# rj11.net
KiCad netlist of a schematic drawn in EAGLE
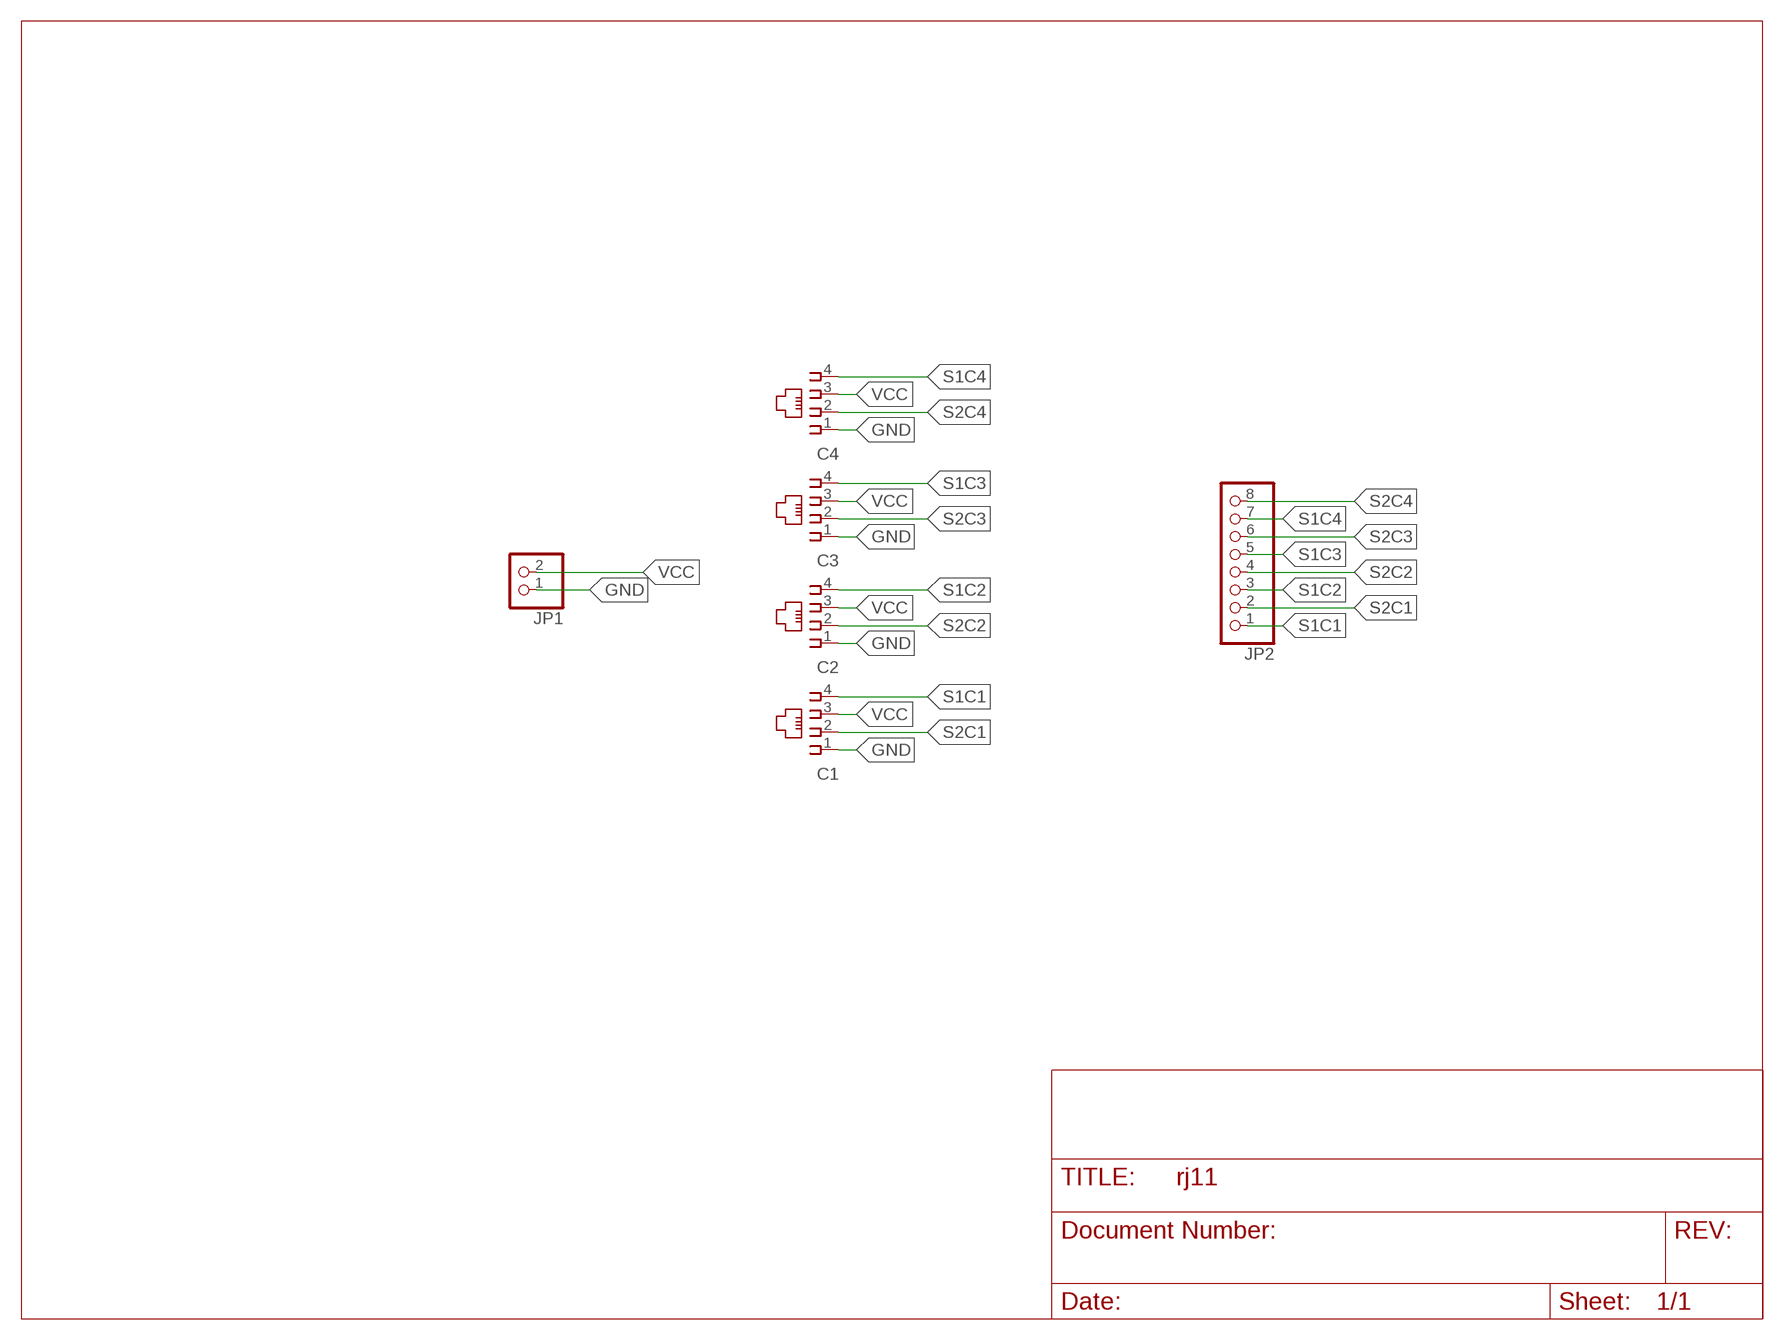
[diagram p0: schematic, sheet 1]

(export (version "E")
  (design (tool "Eeschema 10.0.6"))
  (components
    (comp (ref "C1")
      (value "14867")
      (footprint "eagle-import:14867")
      (libsource (lib "eagle-import") (part "14867"))
    )
    (comp (ref "C2")
      (value "14867")
      (footprint "eagle-import:14867")
      (libsource (lib "eagle-import") (part "14867"))
    )
    (comp (ref "C3")
      (value "14867")
      (footprint "eagle-import:14867")
      (libsource (lib "eagle-import") (part "14867"))
    )
    (comp (ref "C4")
      (value "14867")
      (footprint "eagle-import:14867")
      (libsource (lib "eagle-import") (part "14867"))
    )
    (comp (ref "JP1")
      (value "PINHD-1X2")
      (footprint "eagle-import:1X02")
      (libsource (lib "eagle-import") (part "PINHD-1X2"))
    )
    (comp (ref "JP2")
      (value "PINHD-1X8")
      (footprint "eagle-import:1X08")
      (libsource (lib "eagle-import") (part "PINHD-1X8"))
    )
  )
  (nets
    (net (code "1") (name "GND") (class "Default")
      (node (ref "C1") (pin "1") (pinfunction "1_1") (pintype "passive"))
      (node (ref "C2") (pin "1") (pinfunction "1_1") (pintype "passive"))
      (node (ref "C3") (pin "1") (pinfunction "1_1") (pintype "passive"))
      (node (ref "C4") (pin "1") (pinfunction "1_1") (pintype "passive"))
      (node (ref "JP1") (pin "1") (pinfunction "1_1") (pintype "passive"))
    )
    (net (code "2") (name "S1C1") (class "Default")
      (node (ref "C1") (pin "4") (pinfunction "4_4") (pintype "passive"))
      (node (ref "JP2") (pin "1") (pinfunction "1_1") (pintype "passive"))
    )
    (net (code "3") (name "S1C2") (class "Default")
      (node (ref "C2") (pin "4") (pinfunction "4_4") (pintype "passive"))
      (node (ref "JP2") (pin "3") (pinfunction "3_3") (pintype "passive"))
    )
    (net (code "4") (name "S1C3") (class "Default")
      (node (ref "C3") (pin "4") (pinfunction "4_4") (pintype "passive"))
      (node (ref "JP2") (pin "5") (pinfunction "5_5") (pintype "passive"))
    )
    (net (code "5") (name "S1C4") (class "Default")
      (node (ref "C4") (pin "4") (pinfunction "4_4") (pintype "passive"))
      (node (ref "JP2") (pin "7") (pinfunction "7_7") (pintype "passive"))
    )
    (net (code "6") (name "S2C1") (class "Default")
      (node (ref "C1") (pin "2") (pinfunction "2_2") (pintype "passive"))
      (node (ref "JP2") (pin "2") (pinfunction "2_2") (pintype "passive"))
    )
    (net (code "7") (name "S2C2") (class "Default")
      (node (ref "C2") (pin "2") (pinfunction "2_2") (pintype "passive"))
      (node (ref "JP2") (pin "4") (pinfunction "4_4") (pintype "passive"))
    )
    (net (code "8") (name "S2C3") (class "Default")
      (node (ref "C3") (pin "2") (pinfunction "2_2") (pintype "passive"))
      (node (ref "JP2") (pin "6") (pinfunction "6_6") (pintype "passive"))
    )
    (net (code "9") (name "S2C4") (class "Default")
      (node (ref "C4") (pin "2") (pinfunction "2_2") (pintype "passive"))
      (node (ref "JP2") (pin "8") (pinfunction "8_8") (pintype "passive"))
    )
    (net (code "10") (name "VCC") (class "Default")
      (node (ref "C1") (pin "3") (pinfunction "3_3") (pintype "passive"))
      (node (ref "C2") (pin "3") (pinfunction "3_3") (pintype "passive"))
      (node (ref "C3") (pin "3") (pinfunction "3_3") (pintype "passive"))
      (node (ref "C4") (pin "3") (pinfunction "3_3") (pintype "passive"))
      (node (ref "JP1") (pin "2") (pinfunction "2_2") (pintype "passive"))
    )
  )
)
